# flasher.net
KiCad netlist of a schematic drawn in EAGLE
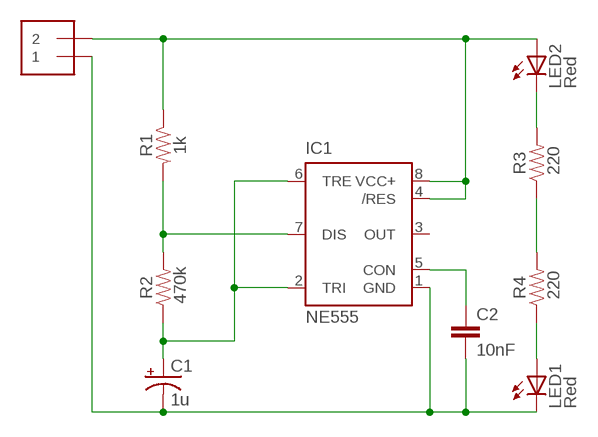
[diagram p0: schematic, sheet 1]

(export (version "E")
  (design (tool "Eeschema 10.0.6"))
  (components
    (comp (ref "C1")
      (value "1u")
      (footprint "eagle-import:CPOL-RADIAL-2.5MM-5MM")
      (libsource (lib "eagle-import") (part "10UF-POLAR-RADIAL-2.5MM-25V-20%"))
    )
    (comp (ref "C2")
      (value "10nF")
      (footprint "eagle-import:CAP-PTH-10MM")
      (libsource (lib "eagle-import") (part "10NF-PTH-10MM-10000V-1-%"))
    )
    (comp (ref "IC1")
      (value "NE555")
      (footprint "eagle-import:DIL-08")
      (fields (field (name "MF") "Arrow Electronics") (field (name "MPN") "NE555N"))
      (libsource (lib "eagle-import") (part "NE555"))
    )
    (comp (ref "J1")
      (value "1X2-3.5MM")
      (footprint "eagle-import:1X2-3.5MM")
      (libsource (lib "eagle-import") (part "1X2-3.5MM"))
    )
    (comp (ref "LED1")
      (value "Red")
      (footprint "eagle-import:LED5MM")
      (libsource (lib "eagle-import") (part "LED5MM"))
    )
    (comp (ref "LED2")
      (value "Red")
      (footprint "eagle-import:LED5MM")
      (libsource (lib "eagle-import") (part "LED5MM"))
    )
    (comp (ref "R1")
      (value "1k")
      (footprint "eagle-import:AXIAL-0.3")
      (libsource (lib "eagle-import") (part "RESISTORAXIAL-0.3"))
    )
    (comp (ref "R2")
      (value "470k")
      (footprint "eagle-import:AXIAL-0.3")
      (libsource (lib "eagle-import") (part "RESISTORAXIAL-0.3"))
    )
    (comp (ref "R3")
      (value "220")
      (footprint "eagle-import:AXIAL-0.3")
      (libsource (lib "eagle-import") (part "RESISTORAXIAL-0.3"))
    )
    (comp (ref "R4")
      (value "220")
      (footprint "eagle-import:AXIAL-0.3")
      (libsource (lib "eagle-import") (part "RESISTORAXIAL-0.3"))
    )
  )
  (nets
    (net (code "1") (name "Net-(C1-+)") (class "Default")
      (node (ref "C1") (pin "1") (pinfunction "+_1") (pintype "passive"))
      (node (ref "IC1") (pin "2") (pinfunction "TRI_2") (pintype "input"))
      (node (ref "IC1") (pin "6") (pinfunction "TRE_6") (pintype "input"))
      (node (ref "R2") (pin "P$1") (pinfunction "1_P$1") (pintype "passive"))
    )
    (net (code "2") (name "Net-(C1--)") (class "Default")
      (node (ref "C1") (pin "2") (pinfunction "-_2") (pintype "passive"))
      (node (ref "C2") (pin "2") (pinfunction "2_2") (pintype "passive"))
      (node (ref "IC1") (pin "1") (pinfunction "GND_1") (pintype "power_in"))
      (node (ref "J1") (pin "1") (pinfunction "1_1") (pintype "passive"))
      (node (ref "LED1") (pin "K") (pinfunction "C_K") (pintype "passive"))
    )
    (net (code "3") (name "Net-(IC1-CON)") (class "Default")
      (node (ref "C2") (pin "1") (pinfunction "1_1") (pintype "passive"))
      (node (ref "IC1") (pin "5") (pinfunction "CON_5") (pintype "input"))
    )
    (net (code "4") (name "Net-(IC1-DIS)") (class "Default")
      (node (ref "IC1") (pin "7") (pinfunction "DIS_7") (pintype "input"))
      (node (ref "R1") (pin "P$2") (pinfunction "2_P$2") (pintype "passive"))
      (node (ref "R2") (pin "P$2") (pinfunction "2_P$2") (pintype "passive"))
    )
    (net (code "5") (name "Net-(IC1-VCC+)") (class "Default")
      (node (ref "IC1") (pin "4") (pinfunction "/RES_4") (pintype "input"))
      (node (ref "IC1") (pin "8") (pinfunction "VCC+_8") (pintype "power_in"))
      (node (ref "J1") (pin "2") (pinfunction "2_2") (pintype "passive"))
      (node (ref "LED2") (pin "A") (pinfunction "A_A") (pintype "passive"))
      (node (ref "R1") (pin "P$1") (pinfunction "1_P$1") (pintype "passive"))
    )
    (net (code "6") (name "Net-(LED2-C)") (class "Default")
      (node (ref "LED2") (pin "K") (pinfunction "C_K") (pintype "passive"))
      (node (ref "R3") (pin "P$2") (pinfunction "2_P$2") (pintype "passive"))
    )
    (net (code "7") (name "Net-(R3-1)") (class "Default")
      (node (ref "R3") (pin "P$1") (pinfunction "1_P$1") (pintype "passive"))
      (node (ref "R4") (pin "P$2") (pinfunction "2_P$2") (pintype "passive"))
    )
    (net (code "8") (name "Net-(R4-1)") (class "Default")
      (node (ref "LED1") (pin "A") (pinfunction "A_A") (pintype "passive"))
      (node (ref "R4") (pin "P$1") (pinfunction "1_P$1") (pintype "passive"))
    )
    (net (code "9") (name "unconnected-(IC1-OUT-Pad3)") (class "Default")
      (node (ref "IC1") (pin "3") (pinfunction "OUT_3") (pintype "output"))
    )
  )
)
